# A-Power.net
KiCad netlist of a schematic drawn in Altium Designer
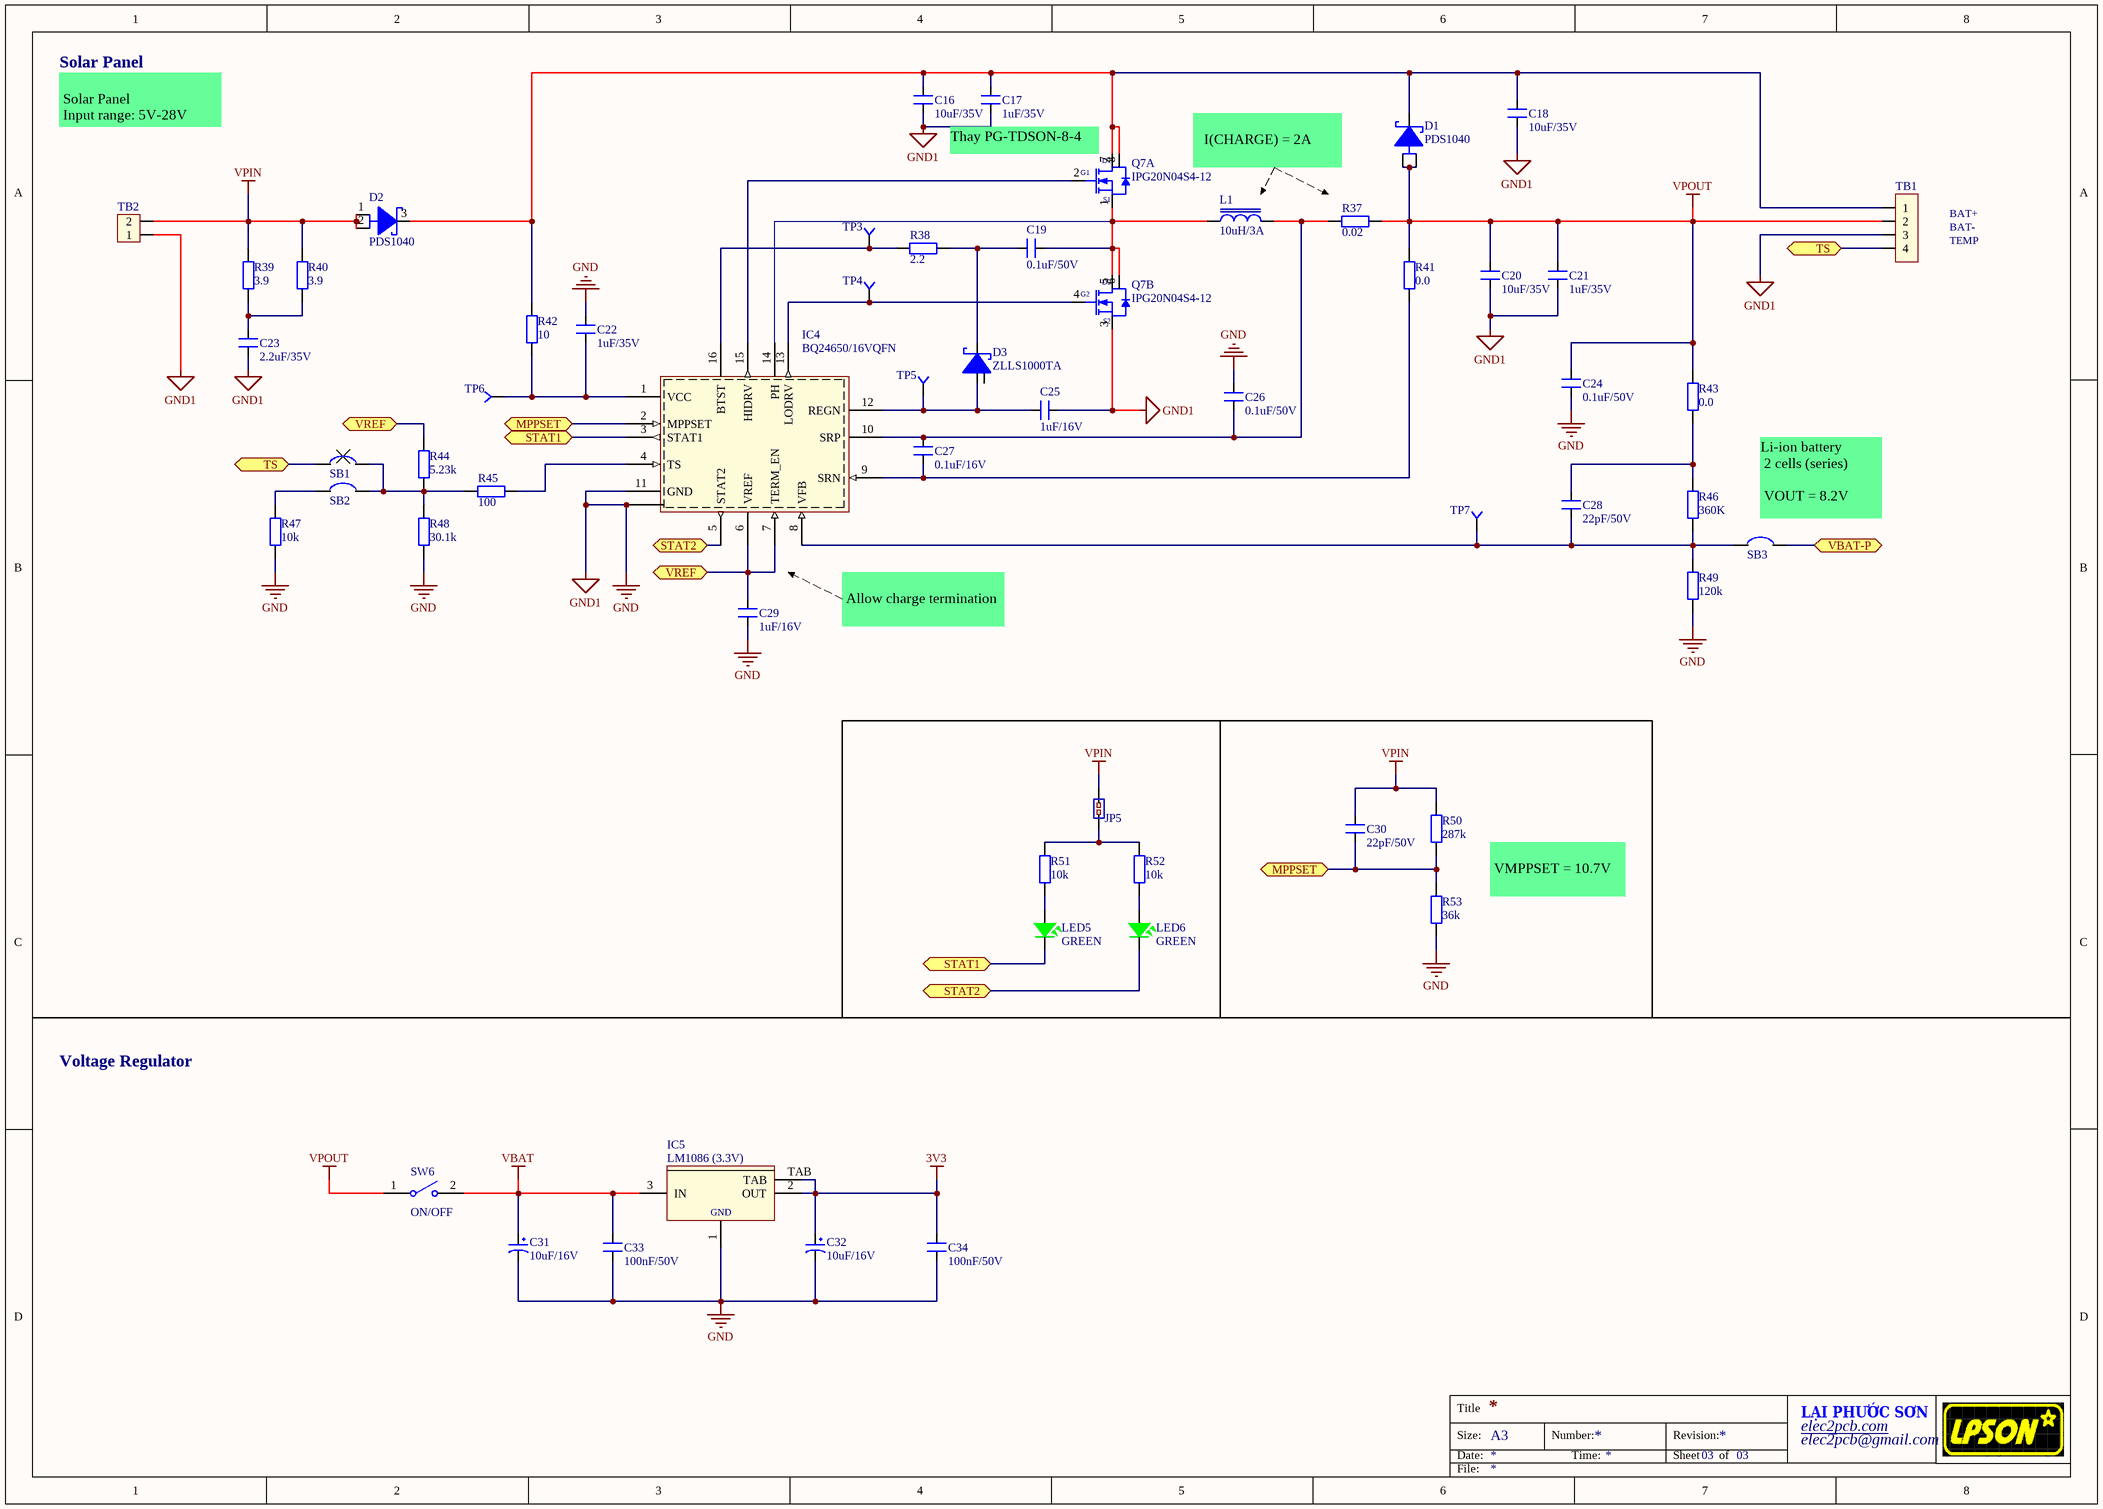
[diagram p0: A-Power.SchDoc]

(export (version "E")
  (design (tool "Eeschema 10.0.6"))
  (components
    (comp (ref "C16")
      (value "10uF/35V")
      (footprint "CAP_CERA_C3216(CC1206INCH)")
      (description "CAP CER 10UF 35V X7R 1206")
      (fields
        (field (name "MANUFACTURER") "Taiyo Yuden")
        (field (name "MANUFACTURER PART NUMBER") "GMK316AB7106KL-TR")
      )
      (libsource (lib "Tran Tuan") (part "CAP-CER/10uF/35V/X7R-1206"))
    )
    (comp (ref "C17")
      (value "1uF/35V")
      (footprint "CAP_CERA_C2012(CC0805INCH)")
      (description "CAP CER 1UF 35V X7R 0805")
      (fields
        (field (name "MANUFACTURER") "Taiyo Yuden")
        (field (name "MANUFACTURER PART NUMBER") "GMK212B7105KG-T")
      )
      (libsource (lib "Tran Tuan") (part "CAP-CER/1uF/35V/X7R/0805"))
    )
    (comp (ref "C18")
      (value "10uF/35V")
      (footprint "CAP_CERA_C3216(CC1206INCH)")
      (description "CAP CER 10UF 35V X7R 1206")
      (fields
        (field (name "MANUFACTURER") "Taiyo Yuden")
        (field (name "MANUFACTURER PART NUMBER") "GMK316AB7106KL-TR")
      )
      (libsource (lib "Tran Tuan") (part "CAP-CER/10uF/35V/X7R-1206"))
    )
    (comp (ref "C19")
      (value "0.1uF/50V")
      (footprint "CAP_CERA_C1608(CC0603INCH)")
      (description "CAP CER 0.1UF 50V X7R 0603")
      (fields
        (field (name "MANUFACTURER") "Kemet")
        (field (name "MANUFACTURER PART NUMBER") "C0603X104K5RACTU")
      )
      (libsource (lib "Tran Tuan") (part "CAP-CER/0.1uF/50V/X7R/0603"))
    )
    (comp (ref "C20")
      (value "10uF/35V")
      (footprint "CAP_CERA_C3216(CC1206INCH)")
      (description "CAP CER 10UF 35V X7R 1206")
      (fields
        (field (name "MANUFACTURER") "Taiyo Yuden")
        (field (name "MANUFACTURER PART NUMBER") "GMK316AB7106KL-TR")
      )
      (libsource (lib "Tran Tuan") (part "CAP-CER/10uF/35V/X7R-1206"))
    )
    (comp (ref "C21")
      (value "1uF/35V")
      (footprint "CAP_CERA_C2012(CC0805INCH)")
      (description "CAP CER 1UF 35V X7R 0805")
      (fields
        (field (name "MANUFACTURER") "Taiyo Yuden")
        (field (name "MANUFACTURER PART NUMBER") "GMK212B7105KG-T")
      )
      (libsource (lib "Tran Tuan") (part "CAP-CER/1uF/35V/X7R/0805"))
    )
    (comp (ref "C22")
      (value "1uF/35V")
      (footprint "CAP_CERA_C2012(CC0805INCH)")
      (description "CAP CER 1UF 35V X7R 0805")
      (fields
        (field (name "MANUFACTURER") "Taiyo Yuden")
        (field (name "MANUFACTURER PART NUMBER") "GMK212B7105KG-T")
      )
      (libsource (lib "Tran Tuan") (part "CAP-CER/1uF/35V/X7R/0805"))
    )
    (comp (ref "C23")
      (value "2.2uF/35V")
      (footprint "CAP_CERA_C3225(CC1210)")
      (description "CAP CER 2.2UF 35V X7R 1210")
      (fields
        (field (name "MANUFACTURER") "Taiyo Yuden")
        (field (name "MANUFACTURER PART NUMBER") "GMK325B7225KNHT")
      )
      (libsource (lib "Tran Tuan") (part "CAP-CER/2.2uF/35V/X7R/1210"))
    )
    (comp (ref "C24")
      (value "0.1uF/50V")
      (footprint "CAP_CERA_C1608(CC0603INCH)")
      (description "CAP CER 0.1UF 50V X7R 0603")
      (fields
        (field (name "MANUFACTURER") "Kemet")
        (field (name "MANUFACTURER PART NUMBER") "C0603X104K5RACTU")
      )
      (libsource (lib "Tran Tuan") (part "CAP-CER/0.1uF/50V/X7R/0603"))
    )
    (comp (ref "C25")
      (value "1uF/16V")
      (footprint "CAP_CERA_C2012(CC0805INCH)")
      (description "CAP CER 1UF 16V X7R 0805")
      (fields
        (field (name "MANUFACTURER") "Kemet")
        (field (name "MANUFACTURER PART NUMBER") "C0805C105K4RACTU")
      )
      (libsource (lib "Tran Tuan") (part "CAP-CER/1uF/16V/X7R/0805"))
    )
    (comp (ref "C26")
      (value "0.1uF/50V")
      (footprint "CAP_CERA_C1608(CC0603INCH)")
      (description "CAP CER 0.1UF 50V X7R 0603")
      (fields
        (field (name "MANUFACTURER") "Kemet")
        (field (name "MANUFACTURER PART NUMBER") "C0603X104K5RACTU")
      )
      (libsource (lib "Tran Tuan") (part "CAP-CER/0.1uF/50V/X7R/0603"))
    )
    (comp (ref "C27")
      (value "0.1uF/16V")
      (footprint "CAP_CERA_C1608(CC0603INCH)")
      (description "CAP CER 0.1UF 16V X7R 0603")
      (fields
        (field (name "MANUFACTURER") "Yageo")
        (field (name "MANUFACTURER PART NUMBER") "CC0603KRX7R7BB104")
      )
      (libsource (lib "Tran Tuan") (part "CAP-CER/0.1uF/16V/X7R/0603"))
    )
    (comp (ref "C28")
      (value "22pF/50V")
      (footprint "CAP_CERA_C1608(CC0603INCH)")
      (description "CAP CER 22PF 50V X7R 0603")
      (fields
        (field (name "MANUFACTURER") "AVX Corporation")
        (field (name "MANUFACTURER PART NUMBER") "06035C220JAT2A")
      )
      (libsource (lib "Tran Tuan") (part "CAP-CER/22pF/50V/X7R/0603"))
    )
    (comp (ref "C29")
      (value "1uF/16V")
      (footprint "CAP_CERA_C2012(CC0805INCH)")
      (description "CAP CER 1UF 16V X7R 0805")
      (fields
        (field (name "MANUFACTURER") "Kemet")
        (field (name "MANUFACTURER PART NUMBER") "C0805C105K4RACTU")
      )
      (libsource (lib "Tran Tuan") (part "CAP-CER/1uF/16V/X7R/0805"))
    )
    (comp (ref "C30")
      (value "22pF/50V")
      (footprint "CAP_CERA_C1608(CC0603INCH)")
      (description "CAP CER 22PF 50V X7R 0603")
      (fields
        (field (name "MANUFACTURER") "AVX Corporation")
        (field (name "MANUFACTURER PART NUMBER") "06035C220JAT2A")
      )
      (libsource (lib "Tran Tuan") (part "CAP-CER/22pF/50V/X7R/0603"))
    )
    (comp (ref "C31")
      (value "10uF/16V")
      (footprint "CAP_CERA_C3216(CC1206INCH)")
      (description "CAP TANT 10UF 16V 10% 1206")
      (fields
        (field (name "MANUFACTURER") "Kemet")
        (field (name "MANUFACTURER PART NUMBER") "T491A106K016AT")
      )
      (libsource (lib "Tran Tuan") (part "CAP-TANT/10uF/16V/1206"))
    )
    (comp (ref "C32")
      (value "10uF/16V")
      (footprint "CAP_CERA_C3216(CC1206INCH)")
      (description "CAP TANT 10UF 16V 10% 1206")
      (fields
        (field (name "MANUFACTURER") "Kemet")
        (field (name "MANUFACTURER PART NUMBER") "T491A106K016AT")
      )
      (libsource (lib "Tran Tuan") (part "CAP-TANT/10uF/16V/1206"))
    )
    (comp (ref "C33")
      (value "100nF/50V")
      (footprint "CAP_CERA_C2012(CC0805INCH)")
      (description "CAP CER 0.1UF 50V X7R 0805")
      (fields
        (field (name "MANUFACTURER") "AVX Corporation")
        (field (name "MANUFACTURER PART NUMBER") "08055C104KAT2A")
      )
      (libsource (lib "Tran Tuan") (part "CAP-CER/100nF/50V/X7R-0805"))
    )
    (comp (ref "C34")
      (value "100nF/50V")
      (footprint "CAP_CERA_C2012(CC0805INCH)")
      (description "CAP CER 0.1UF 50V X7R 0805")
      (fields
        (field (name "MANUFACTURER") "AVX Corporation")
        (field (name "MANUFACTURER PART NUMBER") "08055C104KAT2A")
      )
      (libsource (lib "Tran Tuan") (part "CAP-CER/100nF/50V/X7R-0805"))
    )
    (comp (ref "D1")
      (value "PDS1040")
      (footprint "PDS1040")
      (description "DIODE SCHOTTKY 40V 10A POWERDI5")
      (fields
        (field (name "MANUFACTURER") "Diodes Incorporated")
        (field (name "MANUFACTURER PART NUMBER") "PDS1040-13")
      )
      (libsource (lib "Tran Tuan") (part "DIODE-PDS1040/POWERDI5"))
    )
    (comp (ref "D2")
      (value "PDS1040")
      (footprint "PDS1040")
      (description "DIODE SCHOTTKY 40V 10A POWERDI5")
      (fields
        (field (name "MANUFACTURER") "Diodes Incorporated")
        (field (name "MANUFACTURER PART NUMBER") "PDS1040-13")
      )
      (libsource (lib "") (part "DIODE-PDS1040/POWERDI5_1"))
    )
    (comp (ref "D3")
      (value "ZLLS1000TA")
      (footprint "ZLLS1000")
      (description "DIODE SCHOTTKY 40V 1.16A SOT23-3")
      (fields (field (name "MANUFACTURER") "Diodes Incorporated"))
      (libsource (lib "Tran Tuan") (part "DIODE-ZLLS1000TA/SOT23-3"))
    )
    (comp (ref "IC4")
      (value "BQ24650/16VQFN")
      (footprint "BQ24650-16VQFN")
      (description "IC SYNC SW-MODE BAT CHRGR 16VQFN")
      (fields
        (field (name "MANUFACTURER") "Texas Instruments")
        (field (name "MANUFACTURER PART NUMBER") "BQ24650RVAT")
      )
      (libsource (lib "Tran Tuan") (part "BQ24650/16VQFN"))
    )
    (comp (ref "IC5")
      (value "LM1086 (3.3V)")
      (footprint "LM1086")
      (description "IC REG LDO 3.3V 1.5A DDPAK")
      (fields
        (field (name "MANUFACTURER") "Texas Instruments")
        (field (name "MANUFACTURER PART NUMBER") "LM1086CS-3.3/NOPB")
      )
      (libsource (lib "Tran Tuan") (part "LM1086CS-3.3/NOPB"))
    )
    (comp (ref "JP5")
      (value "JP2-ShortingJumper")
      (footprint "Header_2")
      (description "2.54mm 2-Pin Shorting Jumper")
      (libsource (lib "Tran Tuan") (part "JP2-ShortingJumper"))
    )
    (comp (ref "L1")
      (value "10uH/3A")
      (footprint "IHLP-2525CZ-01")
      (description "FIXED IND 10UH 3A 105mOHM SMD")
      (fields
        (field (name "MANUFACTURER") "Vishay Dale")
        (field (name "MANUFACTURER PART NUMBER") "IHLP2525CZER100M01")
      )
      (libsource (lib "Tran Tuan") (part "IND-10uH/3A/105mOHM"))
    )
    (comp (ref "LED5")
      (value "GREEN")
      (footprint "Led 0805G")
      (description "LED GREEN CLEAR 0805 SMD")
      (fields
        (field (name "MANUFACTURER") "Lite-On Inc.")
        (field (name "MANUFACTURER PART NUMBER") "LTST-C171GKT")
      )
      (libsource (lib "Tran Tuan") (part "LED-GREEN/CLEAR/0805"))
    )
    (comp (ref "LED6")
      (value "GREEN")
      (footprint "Led 0805G")
      (description "LED GREEN CLEAR 0805 SMD")
      (fields
        (field (name "MANUFACTURER") "Lite-On Inc.")
        (field (name "MANUFACTURER PART NUMBER") "LTST-C171GKT")
      )
      (libsource (lib "Tran Tuan") (part "LED-GREEN/CLEAR/0805"))
    )
    (comp (ref "Q7")
      (value "IPG20N04S4-12")
      (footprint "PG-TDSON-8-4")
      (description "MOSFE,T 2N-CH, 40V 20A TDSON-8 OptiMOS-T2")
      (fields (field (name "MANUFACTURER") "Infineon"))
      (libsource (lib "Tran Tuan") (part "MOSFET-IPG20N04S4/TDSON8"))
    )
    (comp (ref "R37")
      (value "~")
      (footprint "RES-1206-3216MM")
      (description "RES SMD 0.02 OHM 1% 1W 1206")
      (fields
        (field (name "MANUFACTURER") "Vishay Dale")
        (field (name "MANUFACTURER PART NUMBER") "WSLP1206R0200FEA")
        (field (name "RESISTANCE (OHMS)") "0.02")
      )
      (libsource (lib "Tran Tuan") (part "RES-1206/±1%"))
    )
    (comp (ref "R38")
      (value "~")
      (footprint "RESC2012(0805)")
      (description "RES SMD 2.2 OHM 5% 1/8W 0805")
      (fields
        (field (name "MANUFACTURER") "Panasonic Electronic Components")
        (field (name "MANUFACTURER PART NUMBER") "ERJ-6GEYJ2R2V")
        (field (name "RESISTANCE (OHMS)") "2.2")
      )
      (libsource (lib "") (part "RES-0805/±5%_1"))
    )
    (comp (ref "R39")
      (value "~")
      (footprint "RES-1206-3216MM")
      (description "RES SMD 3.9 OHM 1% 1/4W 1206")
      (fields
        (field (name "MANUFACTURER") "Panasonic Electronic Components")
        (field (name "MANUFACTURER PART NUMBER") "ERJ-8RQF3R9V")
        (field (name "RESISTANCE (OHMS)") "3.9")
      )
      (libsource (lib "Tran Tuan") (part "RES-1206/±5%"))
    )
    (comp (ref "R40")
      (value "~")
      (footprint "RES-1206-3216MM")
      (description "RES SMD 3.9 OHM 1% 1/4W 1206")
      (fields
        (field (name "MANUFACTURER") "Panasonic Electronic Components")
        (field (name "MANUFACTURER PART NUMBER") "ERJ-8RQF3R9V")
        (field (name "RESISTANCE (OHMS)") "3.9")
      )
      (libsource (lib "Tran Tuan") (part "RES-1206/±5%"))
    )
    (comp (ref "R41")
      (value "~")
      (footprint "RESC2012(0805)")
      (description "RES SMD 0.0 OHM JUMPER 1/8W 0805")
      (fields
        (field (name "MANUFACTURER") "Yageo")
        (field (name "MANUFACTURER PART NUMBER") "RC0805JR-070RL")
        (field (name "RESISTANCE (OHMS)") "0.0")
      )
      (libsource (lib "Tran Tuan") (part "RES-0805/±5%"))
    )
    (comp (ref "R42")
      (value "~")
      (footprint "RESC2012(0805)")
      (description "RES SMD 10 OHM 5% 1/8W 0805")
      (fields
        (field (name "MANUFACTURER") "Yageo")
        (field (name "MANUFACTURER PART NUMBER") "RC0805JR-0710RL")
        (field (name "RESISTANCE (OHMS)") "10")
      )
      (libsource (lib "Tran Tuan") (part "RES-0805/±5%"))
    )
    (comp (ref "R43")
      (value "~")
      (footprint "RESC2012(0805)")
      (description "RES SMD 0.0 OHM JUMPER 1/8W 0805")
      (fields
        (field (name "MANUFACTURER") "Yageo")
        (field (name "MANUFACTURER PART NUMBER") "RC0805JR-070RL")
        (field (name "RESISTANCE (OHMS)") "0.0")
      )
      (libsource (lib "Tran Tuan") (part "RES-0805/±5%"))
    )
    (comp (ref "R44")
      (value "~")
      (footprint "RESC2012(0805)")
      (description "RES SMD 5.23K OHM 1% 1/8W 0805")
      (fields
        (field (name "MANUFACTURER") "Panasonic Electronic Components")
        (field (name "MANUFACTURER PART NUMBER") "ERJ-6ENF5231V")
        (field (name "RESISTANCE (OHMS)") "5.23k")
      )
      (libsource (lib "Tran Tuan") (part "RES-0805/±1%"))
    )
    (comp (ref "R45")
      (value "~")
      (footprint "RESC2012(0805)")
      (description "RES SMD 100 OHM 5% 1/8W 0805")
      (fields
        (field (name "MANUFACTURER") "Panasonic Electronic Components")
        (field (name "MANUFACTURER PART NUMBER") "ERJ-6GEYJ101V")
        (field (name "RESISTANCE (OHMS)") "100")
      )
      (libsource (lib "") (part "RES-0805/±5%_1"))
    )
    (comp (ref "R46")
      (value "360K")
      (footprint "RESC2012(0805)")
      (description "RES SMD 360K OHM 1% 1/8W 0805")
      (fields
        (field (name "MANUFACTURER") "Yageo")
        (field (name "MANUFACTURER PART NUMBER") "RC0805FR-07360KL")
      )
      (libsource (lib "") (part "RES-0805/±1%_1"))
    )
    (comp (ref "R47")
      (value "~")
      (footprint "RESC2012(0805)")
      (description "RES SMD 10K OHM 5% 1/8W 0805")
      (fields
        (field (name "MANUFACTURER") "Yageo")
        (field (name "MANUFACTURER PART NUMBER") "RC0805JR-0710KL")
        (field (name "RESISTANCE (OHMS)") "10k")
      )
      (libsource (lib "Tran Tuan") (part "RES-0805/±5%"))
    )
    (comp (ref "R48")
      (value "~")
      (footprint "RESC2012(0805)")
      (description "RES SMD 30.1K OHM 1% 1/8W 0805")
      (fields
        (field (name "MANUFACTURER") "Yageo")
        (field (name "MANUFACTURER PART NUMBER") "RC0805FR-0730K1L")
        (field (name "RESISTANCE (OHMS)") "30.1k")
      )
      (libsource (lib "Tran Tuan") (part "RES-0805/±1%"))
    )
    (comp (ref "R49")
      (value "~")
      (footprint "RESC2012(0805)")
      (description "RES SMD 120K OHM 1% 1/8W 0805")
      (fields
        (field (name "MANUFACTURER") "Yageo")
        (field (name "MANUFACTURER PART NUMBER") "RC0805FR-07120KL")
        (field (name "RESISTANCE (OHMS)") "120k")
      )
      (libsource (lib "Tran Tuan") (part "RES-0805/±1%"))
    )
    (comp (ref "R50")
      (value "~")
      (footprint "RESC2012(0805)")
      (description "RES SMD 287K OHM 1% 1/8W 0805")
      (fields
        (field (name "MANUFACTURER") "Panasonic Electronic Components")
        (field (name "MANUFACTURER PART NUMBER") "ERJ-6ENF2873V")
        (field (name "RESISTANCE (OHMS)") "287k")
      )
      (libsource (lib "Tran Tuan") (part "RES-0805/±1%"))
    )
    (comp (ref "R51")
      (value "~")
      (footprint "RESC2012(0805)")
      (description "RES SMD 10K OHM 5% 1/8W 0805")
      (fields
        (field (name "MANUFACTURER") "Yageo")
        (field (name "MANUFACTURER PART NUMBER") "RC0805JR-0710KL")
        (field (name "RESISTANCE (OHMS)") "10k")
      )
      (libsource (lib "Tran Tuan") (part "RES-0805/±5%"))
    )
    (comp (ref "R52")
      (value "~")
      (footprint "RESC2012(0805)")
      (description "RES SMD 10K OHM 5% 1/8W 0805")
      (fields
        (field (name "MANUFACTURER") "Yageo")
        (field (name "MANUFACTURER PART NUMBER") "RC0805JR-0710KL")
        (field (name "RESISTANCE (OHMS)") "10k")
      )
      (libsource (lib "Tran Tuan") (part "RES-0805/±5%"))
    )
    (comp (ref "R53")
      (value "~")
      (footprint "RESC2012(0805)")
      (description "RES SMD 36K OHM 1% 1/8W 0805")
      (fields
        (field (name "MANUFACTURER") "Panasonic Electronic Components")
        (field (name "MANUFACTURER PART NUMBER") "ERJ-6ENF3602V")
        (field (name "RESISTANCE (OHMS)") "36k")
      )
      (libsource (lib "") (part "RES-0805/±1%_1"))
    )
    (comp (ref "SB1")
      (value "Not connect")
      (footprint "head PAD")
      (description "Jumper, Connector, 2-pad")
      (libsource (lib "Tran Tuan") (part "Connector-NSB"))
    )
    (comp (ref "SB2")
      (value "Connect")
      (footprint "head PAD")
      (description "Jumper, Connector, 2-pad")
      (libsource (lib "Tran Tuan") (part "Connector-SB"))
    )
    (comp (ref "SB3")
      (value "Connect")
      (footprint "head PAD")
      (description "Jumper, Connector, 2-pad")
      (libsource (lib "Tran Tuan") (part "Connector-SB"))
    )
    (comp (ref "SW6")
      (value "ON/OFF")
      (footprint "SW-POWER")
      (description "SWITCH ROCKER SPST 16A 125V")
      (fields
        (field (name "MANUFACTURER") "TE Connectivity Alcoswitch Switches")
        (field (name "MANUFACTURER PART NUMBER") "PRASA1-16F-BB0BW")
      )
      (libsource (lib "Tran Tuan") (part "SW-ROCKER/SPST/16A"))
    )
    (comp (ref "TB1")
      (value "TERM BLOCK")
      (footprint "MKDS-DOMINO-4-PIN")
      (description "TERM BLOCK 4POS 3.81MM PCB GRN")
      (fields
        (field (name "MANUFACTURER") "Phoenix Contact")
        (field (name "MANUFACTURER PART NUMBER") "1727036")
      )
      (libsource (lib "Tran Tuan") (part "TERM/3.81MM/4POS/GREEN"))
    )
    (comp (ref "TB2")
      (value "TERM BLOCK")
      (footprint "MKDS-DOMINO-2-PIN")
      (description "TERM BLOCK 2POS 3.81MM PCB GRN")
      (fields
        (field (name "MANUFACTURER") "Phoenix Contact")
        (field (name "MANUFACTURER PART NUMBER") "1727010")
      )
      (libsource (lib "Tran Tuan") (part "TERM/3.81MM/2POS/GREEN"))
    )
    (comp (ref "TP3")
      (value "Test Point")
      (footprint "Test_point_VIA06")
      (description "Test Point, Pad, Hole")
      (libsource (lib "Tran Tuan") (part "Connector-TP"))
    )
    (comp (ref "TP4")
      (value "Test Point")
      (footprint "Test_point_VIA06")
      (description "Test Point, Pad, Hole")
      (libsource (lib "Tran Tuan") (part "Connector-TP"))
    )
    (comp (ref "TP5")
      (value "Test Point")
      (footprint "Test_point_VIA06")
      (description "Test Point, Pad, Hole")
      (libsource (lib "Tran Tuan") (part "Connector-TP"))
    )
    (comp (ref "TP6")
      (value "Test Point")
      (footprint "Test_point_VIA06")
      (description "Test Point, Pad, Hole")
      (libsource (lib "Tran Tuan") (part "Connector-TP"))
    )
    (comp (ref "TP7")
      (value "Test Point")
      (footprint "Test_point_VIA06")
      (description "Test Point, Pad, Hole")
      (libsource (lib "Tran Tuan") (part "Connector-TP"))
    )
  )
  (nets
    (net (code "1") (name "/MPPSET") (class "Default")
      (node (ref "C30") (pin "2") (pinfunction "2_2") (pintype "passive"))
      (node (ref "IC4") (pin "2") (pinfunction "MPPSET_2") (pintype "input"))
      (node (ref "R50") (pin "2") (pinfunction "2_2") (pintype "passive"))
      (node (ref "R53") (pin "2") (pinfunction "2_2") (pintype "passive"))
    )
    (net (code "2") (name "/STAT1") (class "Default")
      (node (ref "IC4") (pin "3") (pinfunction "STAT1_3") (pintype "output"))
      (node (ref "LED5") (pin "2") (pinfunction "K_2") (pintype "passive"))
    )
    (net (code "3") (name "/STAT2") (class "Default")
      (node (ref "IC4") (pin "5") (pinfunction "STAT2_5") (pintype "output"))
      (node (ref "LED6") (pin "2") (pinfunction "K_2") (pintype "passive"))
    )
    (net (code "4") (name "/TS") (class "Default")
      (node (ref "SB1") (pin "2") (pinfunction "2_2") (pintype "passive"))
      (node (ref "TB1") (pin "4") (pinfunction "4_4") (pintype "passive"))
    )
    (net (code "5") (name "/VBAT-P") (class "Default")
      (node (ref "SB3") (pin "1") (pinfunction "1_1") (pintype "passive"))
    )
    (net (code "6") (name "/VREF") (class "Default")
      (node (ref "C29") (pin "2") (pinfunction "2_2") (pintype "passive"))
      (node (ref "IC4") (pin "6") (pinfunction "VREF_6") (pintype "power_in"))
      (node (ref "IC4") (pin "7") (pinfunction "TERM_EN_7") (pintype "input"))
      (node (ref "R44") (pin "1") (pinfunction "1_1") (pintype "passive"))
    )
    (net (code "7") (name "3V3") (class "Default")
      (node (ref "C32") (pin "1") (pinfunction "1_1") (pintype "passive"))
      (node (ref "C34") (pin "1") (pinfunction "1_1") (pintype "passive"))
      (node (ref "IC5") (pin "2") (pinfunction "OUT_2") (pintype "power_in"))
      (node (ref "IC5") (pin "TAB") (pinfunction "TAB_TAB") (pintype "power_in"))
    )
    (net (code "8") (name "GND") (class "Default")
      (node (ref "C16") (pin "2") (pinfunction "2_2") (pintype "passive"))
      (node (ref "C17") (pin "2") (pinfunction "2_2") (pintype "passive"))
      (node (ref "C18") (pin "2") (pinfunction "2_2") (pintype "passive"))
      (node (ref "C20") (pin "2") (pinfunction "2_2") (pintype "passive"))
      (node (ref "C21") (pin "2") (pinfunction "2_2") (pintype "passive"))
      (node (ref "C22") (pin "2") (pinfunction "2_2") (pintype "passive"))
      (node (ref "C23") (pin "2") (pinfunction "2_2") (pintype "passive"))
      (node (ref "C24") (pin "1") (pinfunction "1_1") (pintype "passive"))
      (node (ref "C25") (pin "1") (pinfunction "1_1") (pintype "passive"))
      (node (ref "C26") (pin "2") (pinfunction "2_2") (pintype "passive"))
      (node (ref "C29") (pin "1") (pinfunction "1_1") (pintype "passive"))
      (node (ref "C31") (pin "2") (pinfunction "2_2") (pintype "passive"))
      (node (ref "C32") (pin "2") (pinfunction "2_2") (pintype "passive"))
      (node (ref "C33") (pin "2") (pinfunction "2_2") (pintype "passive"))
      (node (ref "C34") (pin "2") (pinfunction "2_2") (pintype "passive"))
      (node (ref "IC4") (pin "11") (pinfunction "GND_11") (pintype "power_in"))
      (node (ref "IC4") (pin "PAD") (pinfunction "PAD_PAD") (pintype "power_in"))
      (node (ref "IC5") (pin "1") (pinfunction "GND_1") (pintype "power_in"))
      (node (ref "Q7") (pin "3") (pinfunction "S2_3") (pintype "passive"))
      (node (ref "R47") (pin "2") (pinfunction "2_2") (pintype "passive"))
      (node (ref "R48") (pin "2") (pinfunction "2_2") (pintype "passive"))
      (node (ref "R49") (pin "2") (pinfunction "2_2") (pintype "passive"))
      (node (ref "R53") (pin "1") (pinfunction "1_1") (pintype "passive"))
      (node (ref "TB1") (pin "3") (pinfunction "3_3") (pintype "passive"))
      (node (ref "TB2") (pin "1") (pinfunction "1_1") (pintype "passive"))
    )
    (net (code "9") (name "Net-(C23-Pad1)") (class "Default")
      (node (ref "C23") (pin "1") (pinfunction "1_1") (pintype "passive"))
      (node (ref "R39") (pin "2") (pinfunction "2_2") (pintype "passive"))
      (node (ref "R40") (pin "2") (pinfunction "2_2") (pintype "passive"))
    )
    (net (code "10") (name "Net-(C28-Pad1)") (class "Default")
      (node (ref "C28") (pin "1") (pinfunction "1_1") (pintype "passive"))
      (node (ref "R43") (pin "2") (pinfunction "2_2") (pintype "passive"))
      (node (ref "R46") (pin "2") (pinfunction "2_2") (pintype "passive"))
    )
    (net (code "11") (name "Net-(D1-K)") (class "Default")
      (node (ref "C16") (pin "1") (pinfunction "1_1") (pintype "passive"))
      (node (ref "C17") (pin "1") (pinfunction "1_1") (pintype "passive"))
      (node (ref "C18") (pin "1") (pinfunction "1_1") (pintype "passive"))
      (node (ref "D1") (pin "3") (pinfunction "K_3") (pintype "passive"))
      (node (ref "D2") (pin "3") (pinfunction "K_3") (pintype "passive"))
      (node (ref "Q7") (pin "7") (pinfunction "D1_7") (pintype "passive"))
      (node (ref "Q7") (pin "8") (pinfunction "D1_8") (pintype "passive"))
      (node (ref "R42") (pin "1") (pinfunction "1_1") (pintype "passive"))
      (node (ref "TB1") (pin "1") (pinfunction "1_1") (pintype "passive"))
    )
    (net (code "12") (name "Net-(D3-A)") (class "Default")
      (node (ref "C25") (pin "2") (pinfunction "2_2") (pintype "passive"))
      (node (ref "D3") (pin "1") (pinfunction "A_1") (pintype "passive"))
      (node (ref "IC4") (pin "12") (pinfunction "REGN_12") (pintype "power_in"))
      (node (ref "TP5") (pin "1") (pinfunction "1_1") (pintype "passive"))
    )
    (net (code "13") (name "Net-(D3-K)") (class "Default")
      (node (ref "C19") (pin "1") (pinfunction "1_1") (pintype "passive"))
      (node (ref "D3") (pin "2") (pinfunction "K_2") (pintype "passive"))
      (node (ref "R38") (pin "2") (pinfunction "2_2") (pintype "passive"))
    )
    (net (code "14") (name "Net-(IC4-BTST)") (class "Default")
      (node (ref "IC4") (pin "16") (pinfunction "BTST_16") (pintype "power_in"))
      (node (ref "R38") (pin "1") (pinfunction "1_1") (pintype "passive"))
      (node (ref "TP3") (pin "1") (pinfunction "1_1") (pintype "passive"))
    )
    (net (code "15") (name "Net-(IC4-HIDRV)") (class "Default")
      (node (ref "IC4") (pin "15") (pinfunction "HIDRV_15") (pintype "output"))
      (node (ref "Q7") (pin "2") (pinfunction "G1_2") (pintype "passive"))
    )
    (net (code "16") (name "Net-(IC4-LODRV)") (class "Default")
      (node (ref "IC4") (pin "13") (pinfunction "LODRV_13") (pintype "output"))
      (node (ref "Q7") (pin "4") (pinfunction "G2_4") (pintype "passive"))
      (node (ref "TP4") (pin "1") (pinfunction "1_1") (pintype "passive"))
    )
    (net (code "17") (name "Net-(IC4-PH)") (class "Default")
      (node (ref "C19") (pin "2") (pinfunction "2_2") (pintype "passive"))
      (node (ref "IC4") (pin "14") (pinfunction "PH_14") (pintype "power_in"))
      (node (ref "L1") (pin "1") (pinfunction "1_1") (pintype "passive"))
      (node (ref "Q7") (pin "1") (pinfunction "S1_1") (pintype "passive"))
      (node (ref "Q7") (pin "5") (pinfunction "D2_5") (pintype "passive"))
      (node (ref "Q7") (pin "6") (pinfunction "D2_6") (pintype "passive"))
    )
    (net (code "18") (name "Net-(IC4-SRN)") (class "Default")
      (node (ref "C27") (pin "2") (pinfunction "2_2") (pintype "passive"))
      (node (ref "IC4") (pin "9") (pinfunction "SRN_9") (pintype "input"))
      (node (ref "R41") (pin "2") (pinfunction "2_2") (pintype "passive"))
    )
    (net (code "19") (name "Net-(IC4-SRP)") (class "Default")
      (node (ref "C26") (pin "1") (pinfunction "1_1") (pintype "passive"))
      (node (ref "C27") (pin "1") (pinfunction "1_1") (pintype "passive"))
      (node (ref "IC4") (pin "10") (pinfunction "SRP_10") (pintype "passive"))
      (node (ref "L1") (pin "2") (pinfunction "2_2") (pintype "passive"))
      (node (ref "R37") (pin "1") (pinfunction "1_1") (pintype "passive"))
    )
    (net (code "20") (name "Net-(IC4-TS)") (class "Default")
      (node (ref "IC4") (pin "4") (pinfunction "TS_4") (pintype "input"))
      (node (ref "R45") (pin "2") (pinfunction "2_2") (pintype "passive"))
    )
    (net (code "21") (name "Net-(IC4-VCC)") (class "Default")
      (node (ref "C22") (pin "1") (pinfunction "1_1") (pintype "passive"))
      (node (ref "IC4") (pin "1") (pinfunction "VCC_1") (pintype "power_in"))
      (node (ref "R42") (pin "2") (pinfunction "2_2") (pintype "passive"))
      (node (ref "TP6") (pin "1") (pinfunction "1_1") (pintype "passive"))
    )
    (net (code "22") (name "Net-(IC4-VFB)") (class "Default")
      (node (ref "C28") (pin "2") (pinfunction "2_2") (pintype "passive"))
      (node (ref "IC4") (pin "8") (pinfunction "VFB_8") (pintype "input"))
      (node (ref "R46") (pin "1") (pinfunction "1_1") (pintype "passive"))
      (node (ref "R49") (pin "1") (pinfunction "1_1") (pintype "passive"))
      (node (ref "SB3") (pin "2") (pinfunction "2_2") (pintype "passive"))
      (node (ref "TP7") (pin "1") (pinfunction "1_1") (pintype "passive"))
    )
    (net (code "23") (name "Net-(JP5-Pad1)") (class "Default")
      (node (ref "JP5") (pin "1") (pinfunction "1_1") (pintype "passive"))
      (node (ref "R51") (pin "1") (pinfunction "1_1") (pintype "passive"))
      (node (ref "R52") (pin "1") (pinfunction "1_1") (pintype "passive"))
    )
    (net (code "24") (name "Net-(LED5-A)") (class "Default")
      (node (ref "LED5") (pin "1") (pinfunction "A_1") (pintype "passive"))
      (node (ref "R51") (pin "2") (pinfunction "2_2") (pintype "passive"))
    )
    (net (code "25") (name "Net-(LED6-A)") (class "Default")
      (node (ref "LED6") (pin "1") (pinfunction "A_1") (pintype "passive"))
      (node (ref "R52") (pin "2") (pinfunction "2_2") (pintype "passive"))
    )
    (net (code "26") (name "Net-(R44-Pad2)") (class "Default")
      (node (ref "R44") (pin "2") (pinfunction "2_2") (pintype "passive"))
      (node (ref "R45") (pin "1") (pinfunction "1_1") (pintype "passive"))
      (node (ref "R48") (pin "1") (pinfunction "1_1") (pintype "passive"))
      (node (ref "SB1") (pin "1") (pinfunction "1_1") (pintype "passive"))
      (node (ref "SB2") (pin "1") (pinfunction "1_1") (pintype "passive"))
    )
    (net (code "27") (name "Net-(R47-Pad1)") (class "Default")
      (node (ref "R47") (pin "1") (pinfunction "1_1") (pintype "passive"))
      (node (ref "SB2") (pin "2") (pinfunction "2_2") (pintype "passive"))
    )
    (net (code "28") (name "VBAT") (class "Default")
      (node (ref "C31") (pin "1") (pinfunction "1_1") (pintype "passive"))
      (node (ref "C33") (pin "1") (pinfunction "1_1") (pintype "passive"))
      (node (ref "IC5") (pin "3") (pinfunction "IN_3") (pintype "power_in"))
      (node (ref "SW6") (pin "2") (pinfunction "2_2") (pintype "passive"))
    )
    (net (code "29") (name "VPIN") (class "Default")
      (node (ref "C30") (pin "1") (pinfunction "1_1") (pintype "passive"))
      (node (ref "D2") (pin "1") (pinfunction "A1_1") (pintype "passive"))
      (node (ref "D2") (pin "2") (pinfunction "A2_2") (pintype "passive"))
      (node (ref "JP5") (pin "2") (pinfunction "2_2") (pintype "passive"))
      (node (ref "R39") (pin "1") (pinfunction "1_1") (pintype "passive"))
      (node (ref "R40") (pin "1") (pinfunction "1_1") (pintype "passive"))
      (node (ref "R50") (pin "1") (pinfunction "1_1") (pintype "passive"))
      (node (ref "TB2") (pin "2") (pinfunction "2_2") (pintype "passive"))
    )
    (net (code "30") (name "VPOUT") (class "Default")
      (node (ref "C20") (pin "1") (pinfunction "1_1") (pintype "passive"))
      (node (ref "C21") (pin "1") (pinfunction "1_1") (pintype "passive"))
      (node (ref "C24") (pin "2") (pinfunction "2_2") (pintype "passive"))
      (node (ref "D1") (pin "1") (pinfunction "A1_1") (pintype "passive"))
      (node (ref "D1") (pin "2") (pinfunction "A2_2") (pintype "passive"))
      (node (ref "R37") (pin "2") (pinfunction "2_2") (pintype "passive"))
      (node (ref "R41") (pin "1") (pinfunction "1_1") (pintype "passive"))
      (node (ref "R43") (pin "1") (pinfunction "1_1") (pintype "passive"))
      (node (ref "SW6") (pin "1") (pinfunction "1_1") (pintype "passive"))
      (node (ref "TB1") (pin "2") (pinfunction "2_2") (pintype "passive"))
    )
    (net (code "31") (name "unconnected-(D3-PadNC)") (class "Default")
      (node (ref "D3") (pin "NC") (pinfunction "NC_NC") (pintype "tri_state"))
    )
  )
)
